# 05_LMS7002M_RF.net
KiCad netlist of a schematic drawn in Altium Designer
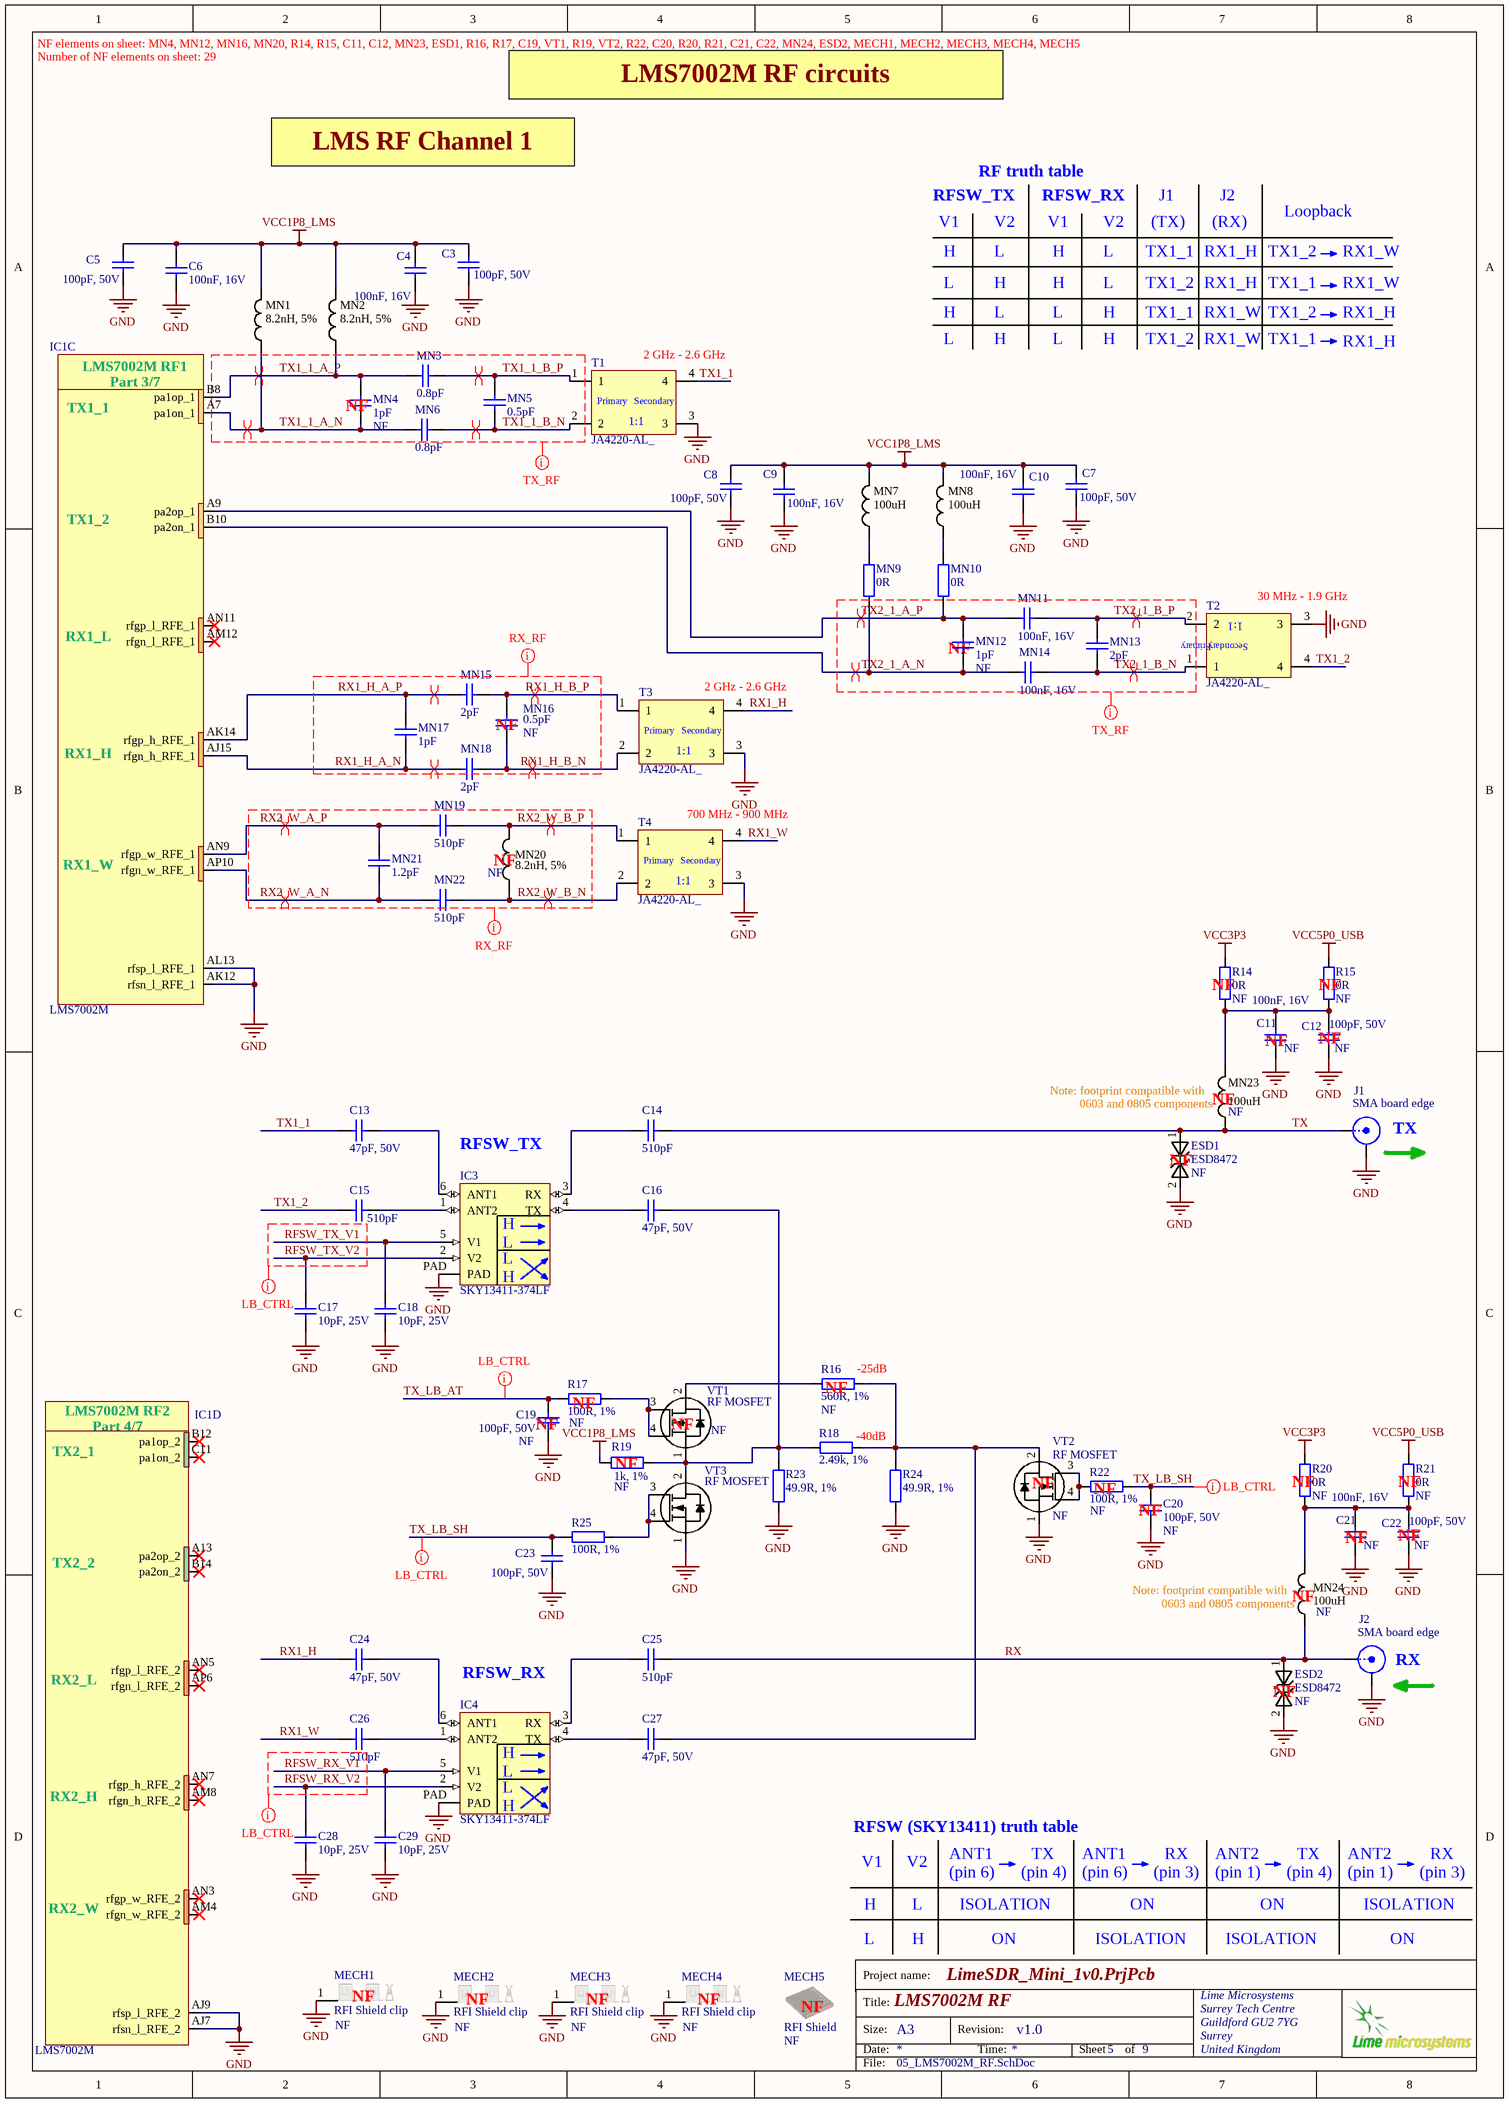
[diagram p0: 05_LMS7002M_RF.SchDoc]

(export (version "E")
  (design (tool "Eeschema 10.0.6"))
  (components
    (comp (ref "C3")
      (value "100pF, 50V")
      (footprint "CAP0402")
      (fields (field (name "TOLERANCE") "±5%") (field (name "MANUFACTURER") "Yageo"))
      (libsource (lib "LimeMicroAltiumLib_schLib") (part "Cap_0402"))
    )
    (comp (ref "C4")
      (value "100nF, 16V")
      (footprint "CAP0402")
      (fields
        (field (name "MANUFACTURER") "Murata Electronics")
        (field (name "TOLERANCE") "10 %")
        (field (name "MANUFACTURER PART NUMBER") "GRM155R71C104KA88D")
      )
      (libsource (lib "LimeMicroAltiumLib_schLib") (part "Cap_0402"))
    )
    (comp (ref "C5")
      (value "100pF, 50V")
      (footprint "CAP0402")
      (fields (field (name "TOLERANCE") "±5%") (field (name "MANUFACTURER") "Yageo"))
      (libsource (lib "LimeMicroAltiumLib_schLib") (part "Cap_0402"))
    )
    (comp (ref "C6")
      (value "100nF, 16V")
      (footprint "CAP0402")
      (fields
        (field (name "MANUFACTURER") "Murata Electronics")
        (field (name "TOLERANCE") "10 %")
        (field (name "MANUFACTURER PART NUMBER") "GRM155R71C104KA88D")
      )
      (libsource (lib "LimeMicroAltiumLib_schLib") (part "Cap_0402"))
    )
    (comp (ref "C7")
      (value "100pF, 50V")
      (footprint "CAP0402")
      (fields (field (name "TOLERANCE") "±5%") (field (name "MANUFACTURER") "Yageo"))
      (libsource (lib "LimeMicroAltiumLib_schLib") (part "Cap_0402"))
    )
    (comp (ref "C8")
      (value "100pF, 50V")
      (footprint "CAP0402")
      (fields (field (name "TOLERANCE") "±5%") (field (name "MANUFACTURER") "Yageo"))
      (libsource (lib "LimeMicroAltiumLib_schLib") (part "Cap_0402"))
    )
    (comp (ref "C9")
      (value "100nF, 16V")
      (footprint "CAP0402")
      (fields
        (field (name "MANUFACTURER") "Murata Electronics")
        (field (name "TOLERANCE") "10 %")
        (field (name "MANUFACTURER PART NUMBER") "GRM155R71C104KA88D")
      )
      (libsource (lib "LimeMicroAltiumLib_schLib") (part "Cap_0402"))
    )
    (comp (ref "C10")
      (value "100nF, 16V")
      (footprint "CAP0402")
      (fields
        (field (name "MANUFACTURER") "Murata Electronics")
        (field (name "TOLERANCE") "10 %")
        (field (name "MANUFACTURER PART NUMBER") "GRM155R71C104KA88D")
      )
      (libsource (lib "LimeMicroAltiumLib_schLib") (part "Cap_0402"))
    )
    (comp (ref "C11")
      (value "100nF, 16V")
      (footprint "CAP0402")
      (fields
        (field (name "ASSEMBLY INFO") "NF")
        (field (name "MANUFACTURER") "Murata Electronics")
        (field (name "TOLERANCE") "10 %")
        (field (name "MANUFACTURER PART NUMBER") "GRM155R71C104KA88D")
      )
      (libsource (lib "LimeMicroAltiumLib_schLib") (part "Cap_0402"))
    )
    (comp (ref "C12")
      (value "100pF, 50V")
      (footprint "CAP0402")
      (fields
        (field (name "ASSEMBLY INFO") "NF")
        (field (name "TOLERANCE") "±5%")
        (field (name "MANUFACTURER") "Yageo")
      )
      (libsource (lib "LimeMicroAltiumLib_schLib") (part "Cap_0402"))
    )
    (comp (ref "C13")
      (value "47pF, 50V")
      (footprint "CAP0402")
      (fields (field (name "TOLERANCE") "±1%") (field (name "MANUFACTURER") "TDK Corporation"))
      (libsource (lib "LimeMicroAltiumLib_schLib") (part "Cap_0402"))
    )
    (comp (ref "C14")
      (value "510pF")
      (footprint "CAP0402")
      (fields
        (field (name "TOLERANCE") "±5%")
        (field (name "MANUFACTURER") "Murata Electronics North America")
        (field (name "MANUFACTURER PART NUMBER") "GRM1555C1H511JA01D")
      )
      (libsource (lib "LimeMicroAltiumLib_schLib") (part "Cap_0402"))
    )
    (comp (ref "C15")
      (value "510pF")
      (footprint "CAP0402")
      (fields
        (field (name "TOLERANCE") "±5%")
        (field (name "MANUFACTURER") "Murata Electronics North America")
        (field (name "MANUFACTURER PART NUMBER") "GRM1555C1H511JA01D")
      )
      (libsource (lib "LimeMicroAltiumLib_schLib") (part "Cap_0402"))
    )
    (comp (ref "C16")
      (value "47pF, 50V")
      (footprint "CAP0402")
      (fields (field (name "TOLERANCE") "±1%") (field (name "MANUFACTURER") "TDK Corporation"))
      (libsource (lib "LimeMicroAltiumLib_schLib") (part "Cap_0402"))
    )
    (comp (ref "C17")
      (value "10pF, 25V")
      (footprint "CAP0402")
      (fields (field (name "MANUFACTURER") "AVX"))
      (libsource (lib "LimeFPGAboard_schLib") (part "Cap_0402"))
    )
    (comp (ref "C18")
      (value "10pF, 25V")
      (footprint "CAP0402")
      (fields (field (name "MANUFACTURER") "AVX"))
      (libsource (lib "LimeFPGAboard_schLib") (part "Cap_0402"))
    )
    (comp (ref "C19")
      (value "100pF, 50V")
      (footprint "CAP0402")
      (fields
        (field (name "ASSEMBLY INFO") "NF")
        (field (name "TOLERANCE") "±5%")
        (field (name "MANUFACTURER") "Yageo")
      )
      (libsource (lib "LimeMicroAltiumLib_schLib") (part "Cap_0402"))
    )
    (comp (ref "C20")
      (value "100pF, 50V")
      (footprint "CAP0402")
      (fields
        (field (name "ASSEMBLY INFO") "NF")
        (field (name "TOLERANCE") "±5%")
        (field (name "MANUFACTURER") "Yageo")
      )
      (libsource (lib "LimeMicroAltiumLib_schLib") (part "Cap_0402"))
    )
    (comp (ref "C21")
      (value "100nF, 16V")
      (footprint "CAP0402")
      (fields
        (field (name "ASSEMBLY INFO") "NF")
        (field (name "MANUFACTURER") "Murata Electronics")
        (field (name "TOLERANCE") "10 %")
        (field (name "MANUFACTURER PART NUMBER") "GRM155R71C104KA88D")
      )
      (libsource (lib "LimeMicroAltiumLib_schLib") (part "Cap_0402"))
    )
    (comp (ref "C22")
      (value "100pF, 50V")
      (footprint "CAP0402")
      (fields
        (field (name "ASSEMBLY INFO") "NF")
        (field (name "TOLERANCE") "±5%")
        (field (name "MANUFACTURER") "Yageo")
      )
      (libsource (lib "LimeMicroAltiumLib_schLib") (part "Cap_0402"))
    )
    (comp (ref "C23")
      (value "100pF, 50V")
      (footprint "CAP0402")
      (fields (field (name "TOLERANCE") "±5%") (field (name "MANUFACTURER") "Yageo"))
      (libsource (lib "LimeMicroAltiumLib_schLib") (part "Cap_0402"))
    )
    (comp (ref "C24")
      (value "47pF, 50V")
      (footprint "CAP0402")
      (fields (field (name "TOLERANCE") "±1%") (field (name "MANUFACTURER") "TDK Corporation"))
      (libsource (lib "LimeMicroAltiumLib_schLib") (part "Cap_0402"))
    )
    (comp (ref "C25")
      (value "510pF")
      (footprint "CAP0402")
      (fields
        (field (name "TOLERANCE") "±5%")
        (field (name "MANUFACTURER") "Murata Electronics North America")
        (field (name "MANUFACTURER PART NUMBER") "GRM1555C1H511JA01D")
      )
      (libsource (lib "LimeMicroAltiumLib_schLib") (part "Cap_0402"))
    )
    (comp (ref "C26")
      (value "510pF")
      (footprint "CAP0402")
      (fields
        (field (name "TOLERANCE") "±5%")
        (field (name "MANUFACTURER") "Murata Electronics North America")
        (field (name "MANUFACTURER PART NUMBER") "GRM1555C1H511JA01D")
      )
      (libsource (lib "LimeMicroAltiumLib_schLib") (part "Cap_0402"))
    )
    (comp (ref "C27")
      (value "47pF, 50V")
      (footprint "CAP0402")
      (fields (field (name "TOLERANCE") "±1%") (field (name "MANUFACTURER") "TDK Corporation"))
      (libsource (lib "LimeMicroAltiumLib_schLib") (part "Cap_0402"))
    )
    (comp (ref "C28")
      (value "10pF, 25V")
      (footprint "CAP0402")
      (fields (field (name "MANUFACTURER") "AVX"))
      (libsource (lib "LimeFPGAboard_schLib") (part "Cap_0402"))
    )
    (comp (ref "C29")
      (value "10pF, 25V")
      (footprint "CAP0402")
      (fields (field (name "MANUFACTURER") "AVX"))
      (libsource (lib "LimeFPGAboard_schLib") (part "Cap_0402"))
    )
    (comp (ref "ESD1")
      (value "ESD8472")
      (footprint "ESD8472_X3DFN2")
      (fields
        (field (name "MANUFACTURER") "ON Semiconductor")
        (field (name "MANUFACTURER PART NUMBER") "ESD8472MUT5G")
        (field (name "ASSEMBLY INFO") "NF")
      )
      (libsource (lib "LimeMicroAltiumLib_schLib") (part "ESD8472"))
    )
    (comp (ref "ESD2")
      (value "ESD8472")
      (footprint "ESD8472_X3DFN2")
      (fields
        (field (name "MANUFACTURER") "ON Semiconductor")
        (field (name "MANUFACTURER PART NUMBER") "ESD8472MUT5G")
        (field (name "ASSEMBLY INFO") "NF")
      )
      (libsource (lib "LimeMicroAltiumLib_schLib") (part "ESD8472"))
    )
    (comp (ref "IC1")
      (value "LMS7002M")
      (footprint "LMS7002M_v4")
      (description "Schematic symbol revision 3. Default footprint - 0.31mm pad")
      (fields (field (name "MANUFACTURER") "Lime Microsystems"))
      (libsource (lib "LimeMicroAltiumLib_schLib") (part "LMS7002Mr3"))
    )
    (comp (ref "IC3")
      (value "SKY13411-374LF")
      (footprint "SKY13411-374LF")
      (fields (field (name "MANUFACTURER") "Skyworks Solutions Inc."))
      (libsource (lib "LimeMicroAltiumLib_schLib") (part "SKY13411-374LF"))
    )
    (comp (ref "IC4")
      (value "SKY13411-374LF")
      (footprint "SKY13411-374LF")
      (fields (field (name "MANUFACTURER") "Skyworks Solutions Inc."))
      (libsource (lib "LimeMicroAltiumLib_schLib") (part "SKY13411-374LF"))
    )
    (comp (ref "J1")
      (value "SMA board edge")
      (footprint "SMA_connector_board_edge_SM")
      (description "CONN SMA JACK STR 50OHM EDGE MNT")
      (fields (field (name "MANUFACTURER") "RF Solutions"))
      (libsource (lib "LimeMicroAltiumLib_schLib") (part "RF_IF_connector"))
    )
    (comp (ref "J2")
      (value "SMA board edge")
      (footprint "SMA_connector_board_edge_SM")
      (description "CONN SMA JACK STR 50OHM EDGE MNT")
      (fields (field (name "MANUFACTURER") "RF Solutions"))
      (libsource (lib "LimeMicroAltiumLib_schLib") (part "RF_IF_connector"))
    )
    (comp (ref "MECH1")
      (value "RFI Shield clip")
      (footprint "RFI_SHIELD_CLPS_MINI")
      (fields (field (name "MANUFACTURER") "HARWIN") (field (name "ASSEMBLY INFO") "NF"))
      (libsource (lib "LimeMicroAltiumLib_schLib") (part "RFI_SHIELD_CLIP"))
    )
    (comp (ref "MECH2")
      (value "RFI Shield clip")
      (footprint "RFI_SHIELD_CLPS_MINI")
      (fields (field (name "MANUFACTURER") "HARWIN") (field (name "ASSEMBLY INFO") "NF"))
      (libsource (lib "LimeMicroAltiumLib_schLib") (part "RFI_SHIELD_CLIP"))
    )
    (comp (ref "MECH3")
      (value "RFI Shield clip")
      (footprint "RFI_SHIELD_CLPS_MINI")
      (fields (field (name "MANUFACTURER") "HARWIN") (field (name "ASSEMBLY INFO") "NF"))
      (libsource (lib "LimeMicroAltiumLib_schLib") (part "RFI_SHIELD_CLIP"))
    )
    (comp (ref "MECH4")
      (value "RFI Shield clip")
      (footprint "RFI_SHIELD_CLPS_MINI")
      (fields (field (name "MANUFACTURER") "HARWIN") (field (name "ASSEMBLY INFO") "NF"))
      (libsource (lib "LimeMicroAltiumLib_schLib") (part "RFI_SHIELD_CLIP"))
    )
    (comp (ref "MECH5")
      (value "RFI Shield")
      (footprint "WurthElectronic_RF_shield")
      (fields (field (name "MANUFACTURER") "WURTH ELEKTRONIK") (field (name "ASSEMBLY INFO") "NF"))
      (libsource (lib "LimeMicroAltiumLib_schLib") (part "RFI_SHIELD_1"))
    )
    (comp (ref "MN1")
      (value "8.2nH, 5%")
      (footprint "RES0402")
      (fields (field (name "MANUFACTURER") "COILCRAFT"))
      (libsource (lib "LimeMicroAltiumLib_schLib") (part "Inductor_0603"))
    )
    (comp (ref "MN2")
      (value "8.2nH, 5%")
      (footprint "RES0402")
      (fields (field (name "MANUFACTURER") "COILCRAFT"))
      (libsource (lib "LimeMicroAltiumLib_schLib") (part "Inductor_0603"))
    )
    (comp (ref "MN3")
      (value "0.8pF")
      (footprint "CAP0402")
      (fields
        (field (name "TOLERANCE") "±0.1pF")
        (field (name "MANUFACTURER") "Murata Electronics North America")
        (field (name "MANUFACTURER PART NUMBER") "GRM1555C1HR80BA01D")
      )
      (libsource (lib "LimeMicroAltiumLib_schLib") (part "Cap_0402"))
    )
    (comp (ref "MN4")
      (value "1pF")
      (footprint "CAP0402")
      (fields
        (field (name "ASSEMBLY INFO") "NF")
        (field (name "MANUFACTURER") "TDK Corporation")
        (field (name "TOLERANCE") "±0.1pF")
      )
      (libsource (lib "LimeMicroAltiumLib_schLib") (part "Cap_0402"))
    )
    (comp (ref "MN5")
      (value "0.5pF")
      (footprint "CAP0402")
      (fields (field (name "TOLERANCE") "±0.25pF") (field (name "MANUFACTURER") "Yageo"))
      (libsource (lib "LimeMicroAltiumLib_schLib") (part "Cap_0402"))
    )
    (comp (ref "MN6")
      (value "0.8pF")
      (footprint "CAP0402")
      (fields
        (field (name "TOLERANCE") "±0.1pF")
        (field (name "MANUFACTURER") "Murata Electronics North America")
        (field (name "MANUFACTURER PART NUMBER") "GRM1555C1HR80BA01D")
      )
      (libsource (lib "LimeMicroAltiumLib_schLib") (part "Cap_0402"))
    )
    (comp (ref "MN7")
      (value "100uH")
      (footprint "RES0805")
      (fields
        (field (name "TOLERANCE") "±10%")
        (field (name "MANUFACTURER") "TDK Corporation")
        (field (name "MANUFACTURER PART NUMBER") "MLF2012C101KT000")
      )
      (libsource (lib "LimeMicroAltiumLib_schLib") (part "Inductor_0603"))
    )
    (comp (ref "MN8")
      (value "100uH")
      (footprint "RES0805")
      (fields
        (field (name "TOLERANCE") "±10%")
        (field (name "MANUFACTURER") "TDK Corporation")
        (field (name "MANUFACTURER PART NUMBER") "MLF2012C101KT000")
      )
      (libsource (lib "LimeMicroAltiumLib_schLib") (part "Inductor_0603"))
    )
    (comp (ref "MN9")
      (value "0R")
      (footprint "RES0402")
      (fields (field (name "MANUFACTURER") "Yageo"))
      (libsource (lib "LimeFPGAboard_schLib") (part "Res_0402"))
    )
    (comp (ref "MN10")
      (value "0R")
      (footprint "RES0402")
      (fields (field (name "MANUFACTURER") "Yageo"))
      (libsource (lib "LimeFPGAboard_schLib") (part "Res_0402"))
    )
    (comp (ref "MN11")
      (value "100nF, 16V")
      (footprint "CAP0402")
      (fields
        (field (name "MANUFACTURER") "Murata Electronics")
        (field (name "TOLERANCE") "10 %")
        (field (name "MANUFACTURER PART NUMBER") "GRM155R71C104KA88D")
      )
      (libsource (lib "LimeMicroAltiumLib_schLib") (part "Cap_0402"))
    )
    (comp (ref "MN12")
      (value "1pF")
      (footprint "CAP0402")
      (fields
        (field (name "ASSEMBLY INFO") "NF")
        (field (name "MANUFACTURER") "TDK Corporation")
        (field (name "TOLERANCE") "±0.1pF")
      )
      (libsource (lib "LimeMicroAltiumLib_schLib") (part "Cap_0402"))
    )
    (comp (ref "MN13")
      (value "2pF")
      (footprint "CAP0402")
      (fields (field (name "MANUFACTURER PART NUMBER") "04025U2R0BAT2A") (field (name "MANUFACTURER") "AVX"))
      (libsource (lib "LimeMicroAltiumLib_schLib") (part "Cap_0402"))
    )
    (comp (ref "MN14")
      (value "100nF, 16V")
      (footprint "CAP0402")
      (fields
        (field (name "MANUFACTURER") "Murata Electronics")
        (field (name "TOLERANCE") "10 %")
        (field (name "MANUFACTURER PART NUMBER") "GRM155R71C104KA88D")
      )
      (libsource (lib "LimeMicroAltiumLib_schLib") (part "Cap_0402"))
    )
    (comp (ref "MN15")
      (value "2pF")
      (footprint "CAP0402")
      (fields (field (name "MANUFACTURER PART NUMBER") "04025U2R0BAT2A") (field (name "MANUFACTURER") "AVX"))
      (libsource (lib "LimeMicroAltiumLib_schLib") (part "Cap_0402"))
    )
    (comp (ref "MN16")
      (value "0.5pF")
      (footprint "CAP0402")
      (fields
        (field (name "ASSEMBLY INFO") "NF")
        (field (name "TOLERANCE") "±0.25pF")
        (field (name "MANUFACTURER") "Yageo")
      )
      (libsource (lib "LimeMicroAltiumLib_schLib") (part "Cap_0402"))
    )
    (comp (ref "MN17")
      (value "1pF")
      (footprint "CAP0402")
      (fields (field (name "MANUFACTURER") "TDK Corporation") (field (name "TOLERANCE") "±0.1pF"))
      (libsource (lib "LimeMicroAltiumLib_schLib") (part "Cap_0402"))
    )
    (comp (ref "MN18")
      (value "2pF")
      (footprint "CAP0402")
      (fields (field (name "MANUFACTURER PART NUMBER") "04025U2R0BAT2A") (field (name "MANUFACTURER") "AVX"))
      (libsource (lib "LimeMicroAltiumLib_schLib") (part "Cap_0402"))
    )
    (comp (ref "MN19")
      (value "510pF")
      (footprint "CAP0402")
      (fields
        (field (name "TOLERANCE") "±5%")
        (field (name "MANUFACTURER") "Murata Electronics North America")
        (field (name "MANUFACTURER PART NUMBER") "GRM1555C1H511JA01D")
      )
      (libsource (lib "LimeMicroAltiumLib_schLib") (part "Cap_0402"))
    )
    (comp (ref "MN20")
      (value "8.2nH, 5%")
      (footprint "RES0402")
      (fields (field (name "MANUFACTURER") "COILCRAFT") (field (name "ASSEMBLY INFO") "NF"))
      (libsource (lib "LimeMicroAltiumLib_schLib") (part "Inductor_0603"))
    )
    (comp (ref "MN21")
      (value "1.2pF")
      (footprint "CAP0402")
      (fields
        (field (name "MANUFACTURER") "Murata Electronics North America")
        (field (name "TOLERANCE") "±0.25pF")
      )
      (libsource (lib "LimeMicroAltiumLib_schLib") (part "Cap_0402"))
    )
    (comp (ref "MN22")
      (value "510pF")
      (footprint "CAP0402")
      (fields
        (field (name "TOLERANCE") "±5%")
        (field (name "MANUFACTURER") "Murata Electronics North America")
        (field (name "MANUFACTURER PART NUMBER") "GRM1555C1H511JA01D")
      )
      (libsource (lib "LimeMicroAltiumLib_schLib") (part "Cap_0402"))
    )
    (comp (ref "MN23")
      (value "100uH")
      (footprint "RES0805_0603")
      (fields
        (field (name "TOLERANCE") "±10%")
        (field (name "MANUFACTURER") "TDK Corporation")
        (field (name "MANUFACTURER PART NUMBER") "MLF2012C101KT000")
        (field (name "ASSEMBLY INFO") "NF")
      )
      (libsource (lib "LimeMicroAltiumLib_schLib") (part "Inductor_0603"))
    )
    (comp (ref "MN24")
      (value "100uH")
      (footprint "RES0805_0603")
      (fields
        (field (name "TOLERANCE") "±10%")
        (field (name "MANUFACTURER") "TDK Corporation")
        (field (name "MANUFACTURER PART NUMBER") "MLF2012C101KT000")
        (field (name "ASSEMBLY INFO") "NF")
      )
      (libsource (lib "LimeMicroAltiumLib_schLib") (part "Inductor_0603"))
    )
    (comp (ref "R14")
      (value "0R")
      (footprint "RES0402")
      (fields (field (name "MANUFACTURER") "Yageo") (field (name "ASSEMBLY INFO") "NF"))
      (libsource (lib "LimeFPGAboard_schLib") (part "Res_0402"))
    )
    (comp (ref "R15")
      (value "0R")
      (footprint "RES0402")
      (fields (field (name "MANUFACTURER") "Yageo") (field (name "ASSEMBLY INFO") "NF"))
      (libsource (lib "LimeFPGAboard_schLib") (part "Res_0402"))
    )
    (comp (ref "R16")
      (value "560R, 1%")
      (footprint "RES0402")
      (fields
        (field (name "ASSEMBLY INFO") "NF")
        (field (name "MANUFACTURER PART NUMBER") "CRCW0402560RFKED")
        (field (name "TOLERANCE") "±1%")
        (field (name "MANUFACTURER") "Vishay Dale")
      )
      (libsource (lib "LimeMicroAltiumLib_schLib") (part "Res_0402"))
    )
    (comp (ref "R17")
      (value "100R, 1%")
      (footprint "RES0402")
      (fields
        (field (name "TOLERANCE") "±1%")
        (field (name "MANUFACTURER") "Stackpole Electronics Inc.")
        (field (name "ASSEMBLY INFO") "NF")
      )
      (libsource (lib "LimeFPGAboard_schLib") (part "Res_0402"))
    )
    (comp (ref "R18")
      (value "2.49k, 1%")
      (footprint "RES0402")
      (fields
        (field (name "TOLERANCE") "±1%")
        (field (name "MANUFACTURER PART NUMBER") "RC0402FR-072K49L")
        (field (name "MANUFACTURER") "Yageo")
      )
      (libsource (lib "LimeMicroAltiumLib_schLib") (part "Res_0402"))
    )
    (comp (ref "R19")
      (value "1k, 1%")
      (footprint "RES0402")
      (fields
        (field (name "ASSEMBLY INFO") "NF")
        (field (name "MANUFACTURER") "Stackpole Electronics Inc")
        (field (name "TOLERANCE") "±1%")
      )
      (libsource (lib "LimeMicroAltiumLib_schLib") (part "Res_0402"))
    )
    (comp (ref "R20")
      (value "0R")
      (footprint "RES0402")
      (fields (field (name "MANUFACTURER") "Yageo") (field (name "ASSEMBLY INFO") "NF"))
      (libsource (lib "LimeFPGAboard_schLib") (part "Res_0402"))
    )
    (comp (ref "R21")
      (value "0R")
      (footprint "RES0402")
      (fields (field (name "MANUFACTURER") "Yageo") (field (name "ASSEMBLY INFO") "NF"))
      (libsource (lib "LimeFPGAboard_schLib") (part "Res_0402"))
    )
    (comp (ref "R22")
      (value "100R, 1%")
      (footprint "RES0402")
      (fields
        (field (name "TOLERANCE") "±1%")
        (field (name "MANUFACTURER") "Stackpole Electronics Inc.")
        (field (name "ASSEMBLY INFO") "NF")
      )
      (libsource (lib "LimeFPGAboard_schLib") (part "Res_0402"))
    )
    (comp (ref "R23")
      (value "49.9R, 1%")
      (footprint "RES0402")
      (fields
        (field (name "TOLERANCE") "±1%")
        (field (name "MANUFACTURER") "Samsung Electro-Mechanics America, Inc.")
        (field (name "MANUFACTURER PART NUMBER") "RC1005F49R9CS")
      )
      (libsource (lib "LimeMicroAltiumLib_schLib") (part "Res_0402"))
    )
    (comp (ref "R24")
      (value "49.9R, 1%")
      (footprint "RES0402")
      (fields
        (field (name "TOLERANCE") "±1%")
        (field (name "MANUFACTURER") "Samsung Electro-Mechanics America, Inc.")
        (field (name "MANUFACTURER PART NUMBER") "RC1005F49R9CS")
      )
      (libsource (lib "LimeMicroAltiumLib_schLib") (part "Res_0402"))
    )
    (comp (ref "R25")
      (value "100R, 1%")
      (footprint "RES0402")
      (fields (field (name "TOLERANCE") "±1%") (field (name "MANUFACTURER") "Stackpole Electronics Inc."))
      (libsource (lib "LimeFPGAboard_schLib") (part "Res_0402"))
    )
    (comp (ref "T1")
      (value "JA4220-AL_")
      (footprint "JA4220-AL_")
      (fields (field (name "MANUFACTURER") "Coilcraft"))
      (libsource (lib "LimeMicroAltiumLib_schLib") (part "JA4220-AL_"))
    )
    (comp (ref "T2")
      (value "JA4220-AL_")
      (footprint "JA4220-AL_")
      (fields (field (name "MANUFACTURER") "Coilcraft"))
      (libsource (lib "") (part "JA4220-AL__1"))
    )
    (comp (ref "T3")
      (value "JA4220-AL_")
      (footprint "JA4220-AL_")
      (fields (field (name "MANUFACTURER") "Coilcraft"))
      (libsource (lib "LimeMicroAltiumLib_schLib") (part "JA4220-AL_"))
    )
    (comp (ref "T4")
      (value "JA4220-AL_")
      (footprint "JA4220-AL_")
      (fields (field (name "MANUFACTURER") "Coilcraft"))
      (libsource (lib "LimeMicroAltiumLib_schLib") (part "JA4220-AL_"))
    )
    (comp (ref "VT1")
      (value "RF MOSFET")
      (footprint "BF1105R_SOT143R4")
      (fields (field (name "MANUFACTURER") "NXP Semiconductors") (field (name "ASSEMBLY INFO") "NF"))
      (libsource (lib "LimeMicroAltiumLib_schLib") (part "BF1105R,215"))
    )
    (comp (ref "VT2")
      (value "RF MOSFET")
      (footprint "BF1105R_SOT143R4")
      (fields (field (name "MANUFACTURER") "NXP Semiconductors") (field (name "ASSEMBLY INFO") "NF"))
      (libsource (lib "LimeMicroAltiumLib_schLib") (part "BF1105R,215"))
    )
    (comp (ref "VT3")
      (value "RF MOSFET")
      (footprint "BF1105R_SOT143R4")
      (fields (field (name "MANUFACTURER") "NXP Semiconductors"))
      (libsource (lib "LimeMicroAltiumLib_schLib") (part "BF1105R,215"))
    )
  )
  (nets
    (net (code "1") (name "/RFSW_RX_V1") (class "Default")
      (node (ref "C29") (pin "2") (pinfunction "2_2") (pintype "passive"))
      (node (ref "IC4") (pin "5") (pinfunction "V1_5") (pintype "input"))
    )
    (net (code "2") (name "/RFSW_RX_V2") (class "Default")
      (node (ref "C28") (pin "2") (pinfunction "2_2") (pintype "passive"))
      (node (ref "IC4") (pin "2") (pinfunction "V2_2") (pintype "input"))
    )
    (net (code "3") (name "/RFSW_TX_V1") (class "Default")
      (node (ref "C18") (pin "2") (pinfunction "2_2") (pintype "passive"))
      (node (ref "IC3") (pin "5") (pinfunction "V1_5") (pintype "input"))
    )
    (net (code "4") (name "/RFSW_TX_V2") (class "Default")
      (node (ref "C17") (pin "2") (pinfunction "2_2") (pintype "passive"))
      (node (ref "IC3") (pin "2") (pinfunction "V2_2") (pintype "input"))
    )
    (net (code "5") (name "/RX") (class "Default")
      (node (ref "C25") (pin "2") (pinfunction "2_2") (pintype "passive"))
      (node (ref "ESD2") (pin "1") (pinfunction "1_1") (pintype "passive"))
      (node (ref "J2") (pin "1") (pinfunction "X_1") (pintype "passive"))
      (node (ref "MN24") (pin "1") (pinfunction "1_1") (pintype "passive"))
    )
    (net (code "6") (name "/RX1_H") (class "Default")
      (node (ref "C24") (pin "2") (pinfunction "2_2") (pintype "passive"))
      (node (ref "T3") (pin "4") (pinfunction "4_4") (pintype "passive"))
    )
    (net (code "7") (name "/RX1_H_A_N") (class "Default")
      (node (ref "IC1") (pin "AJ15") (pinfunction "rfgn_h_RFE_1_AJ15") (pintype "passive"))
      (node (ref "MN17") (pin "1") (pinfunction "1_1") (pintype "passive"))
      (node (ref "MN18") (pin "2") (pinfunction "2_2") (pintype "passive"))
    )
    (net (code "8") (name "/RX1_H_A_P") (class "Default")
      (node (ref "IC1") (pin "AK14") (pinfunction "rfgp_h_RFE_1_AK14") (pintype "passive"))
      (node (ref "MN15") (pin "2") (pinfunction "2_2") (pintype "passive"))
      (node (ref "MN17") (pin "2") (pinfunction "2_2") (pintype "passive"))
    )
    (net (code "9") (name "/RX1_H_B_N") (class "Default")
      (node (ref "MN16") (pin "1") (pinfunction "1_1") (pintype "passive"))
      (node (ref "MN18") (pin "1") (pinfunction "1_1") (pintype "passive"))
      (node (ref "T3") (pin "2") (pinfunction "2_2") (pintype "passive"))
    )
    (net (code "10") (name "/RX1_H_B_P") (class "Default")
      (node (ref "MN15") (pin "1") (pinfunction "1_1") (pintype "passive"))
      (node (ref "MN16") (pin "2") (pinfunction "2_2") (pintype "passive"))
      (node (ref "T3") (pin "1") (pinfunction "1_1") (pintype "passive"))
    )
    (net (code "11") (name "/RX1_W") (class "Default")
      (node (ref "C26") (pin "2") (pinfunction "2_2") (pintype "passive"))
      (node (ref "T4") (pin "4") (pinfunction "4_4") (pintype "passive"))
    )
    (net (code "12") (name "/RX2_W_A_N") (class "Default")
      (node (ref "IC1") (pin "AP10") (pinfunction "rfgn_w_RFE_1_AP10") (pintype "passive"))
      (node (ref "MN21") (pin "1") (pinfunction "1_1") (pintype "passive"))
      (node (ref "MN22") (pin "2") (pinfunction "2_2") (pintype "passive"))
    )
    (net (code "13") (name "/RX2_W_A_P") (class "Default")
      (node (ref "IC1") (pin "AN9") (pinfunction "rfgp_w_RFE_1_AN9") (pintype "passive"))
      (node (ref "MN19") (pin "2") (pinfunction "2_2") (pintype "passive"))
      (node (ref "MN21") (pin "2") (pinfunction "2_2") (pintype "passive"))
    )
    (net (code "14") (name "/RX2_W_B_N") (class "Default")
      (node (ref "MN20") (pin "1") (pinfunction "1_1") (pintype "passive"))
      (node (ref "MN22") (pin "1") (pinfunction "1_1") (pintype "passive"))
      (node (ref "T4") (pin "2") (pinfunction "2_2") (pintype "passive"))
    )
    (net (code "15") (name "/RX2_W_B_P") (class "Default")
      (node (ref "MN19") (pin "1") (pinfunction "1_1") (pintype "passive"))
      (node (ref "MN20") (pin "2") (pinfunction "2_2") (pintype "passive"))
      (node (ref "T4") (pin "1") (pinfunction "1_1") (pintype "passive"))
    )
    (net (code "16") (name "/TX") (class "Default")
      (node (ref "C14") (pin "2") (pinfunction "2_2") (pintype "passive"))
      (node (ref "ESD1") (pin "1") (pinfunction "1_1") (pintype "passive"))
      (node (ref "J1") (pin "1") (pinfunction "X_1") (pintype "passive"))
      (node (ref "MN23") (pin "1") (pinfunction "1_1") (pintype "passive"))
    )
    (net (code "17") (name "/TX1_1") (class "Default")
      (node (ref "C13") (pin "2") (pinfunction "2_2") (pintype "passive"))
      (node (ref "T1") (pin "4") (pinfunction "4_4") (pintype "passive"))
    )
    (net (code "18") (name "/TX1_1_A_N") (class "Default")
      (node (ref "IC1") (pin "A7") (pinfunction "pa1on_1_A7") (pintype "passive"))
      (node (ref "MN1") (pin "1") (pinfunction "1_1") (pintype "passive"))
      (node (ref "MN4") (pin "1") (pinfunction "1_1") (pintype "passive"))
      (node (ref "MN6") (pin "2") (pinfunction "2_2") (pintype "passive"))
    )
    (net (code "19") (name "/TX1_1_A_P") (class "Default")
      (node (ref "IC1") (pin "B8") (pinfunction "pa1op_1_B8") (pintype "passive"))
      (node (ref "MN2") (pin "1") (pinfunction "1_1") (pintype "passive"))
      (node (ref "MN3") (pin "1") (pinfunction "1_1") (pintype "passive"))
      (node (ref "MN4") (pin "2") (pinfunction "2_2") (pintype "passive"))
    )
    (net (code "20") (name "/TX1_1_B_N") (class "Default")
      (node (ref "MN5") (pin "2") (pinfunction "2_2") (pintype "passive"))
      (node (ref "MN6") (pin "1") (pinfunction "1_1") (pintype "passive"))
      (node (ref "T1") (pin "2") (pinfunction "2_2") (pintype "passive"))
    )
    (net (code "21") (name "/TX1_1_B_P") (class "Default")
      (node (ref "MN3") (pin "2") (pinfunction "2_2") (pintype "passive"))
      (node (ref "MN5") (pin "1") (pinfunction "1_1") (pintype "passive"))
      (node (ref "T1") (pin "1") (pinfunction "1_1") (pintype "passive"))
    )
    (net (code "22") (name "/TX1_2") (class "Default")
      (node (ref "C15") (pin "2") (pinfunction "2_2") (pintype "passive"))
      (node (ref "T2") (pin "4") (pinfunction "4_4") (pintype "passive"))
    )
    (net (code "23") (name "/TX2_1_A_N") (class "Default")
      (node (ref "IC1") (pin "B10") (pinfunction "pa2on_1_B10") (pintype "passive"))
      (node (ref "MN12") (pin "2") (pinfunction "2_2") (pintype "passive"))
      (node (ref "MN14") (pin "1") (pinfunction "1_1") (pintype "passive"))
      (node (ref "MN9") (pin "1") (pinfunction "1_1") (pintype "passive"))
    )
    (net (code "24") (name "/TX2_1_A_P") (class "Default")
      (node (ref "IC1") (pin "A9") (pinfunction "pa2op_1_A9") (pintype "passive"))
      (node (ref "MN10") (pin "1") (pinfunction "1_1") (pintype "passive"))
      (node (ref "MN11") (pin "2") (pinfunction "2_2") (pintype "passive"))
      (node (ref "MN12") (pin "1") (pinfunction "1_1") (pintype "passive"))
    )
    (net (code "25") (name "/TX2_1_B_N") (class "Default")
      (node (ref "MN13") (pin "1") (pinfunction "1_1") (pintype "passive"))
      (node (ref "MN14") (pin "2") (pinfunction "2_2") (pintype "passive"))
      (node (ref "T2") (pin "1") (pinfunction "1_1") (pintype "passive"))
    )
    (net (code "26") (name "/TX2_1_B_P") (class "Default")
      (node (ref "MN11") (pin "1") (pinfunction "1_1") (pintype "passive"))
      (node (ref "MN13") (pin "2") (pinfunction "2_2") (pintype "passive"))
      (node (ref "T2") (pin "2") (pinfunction "2_2") (pintype "passive"))
    )
    (net (code "27") (name "/TX_LB_AT") (class "Default")
      (node (ref "C19") (pin "1") (pinfunction "1_1") (pintype "passive"))
      (node (ref "R17") (pin "2") (pinfunction "2_2") (pintype "passive"))
    )
    (net (code "28") (name "/TX_LB_SH") (class "Default")
      (node (ref "C20") (pin "1") (pinfunction "1_1") (pintype "passive"))
      (node (ref "C23") (pin "1") (pinfunction "1_1") (pintype "passive"))
      (node (ref "R22") (pin "1") (pinfunction "1_1") (pintype "passive"))
      (node (ref "R25") (pin "2") (pinfunction "2_2") (pintype "passive"))
    )
    (net (code "29") (name "GND") (class "Default")
      (node (ref "C10") (pin "1") (pinfunction "1_1") (pintype "passive"))
      (node (ref "C11") (pin "1") (pinfunction "1_1") (pintype "passive"))
      (node (ref "C12") (pin "2") (pinfunction "2_2") (pintype "passive"))
      (node (ref "C17") (pin "1") (pinfunction "1_1") (pintype "passive"))
      (node (ref "C18") (pin "1") (pinfunction "1_1") (pintype "passive"))
      (node (ref "C19") (pin "2") (pinfunction "2_2") (pintype "passive"))
      (node (ref "C20") (pin "2") (pinfunction "2_2") (pintype "passive"))
      (node (ref "C21") (pin "1") (pinfunction "1_1") (pintype "passive"))
      (node (ref "C22") (pin "2") (pinfunction "2_2") (pintype "passive"))
      (node (ref "C23") (pin "2") (pinfunction "2_2") (pintype "passive"))
      (node (ref "C28") (pin "1") (pinfunction "1_1") (pintype "passive"))
      (node (ref "C29") (pin "1") (pinfunction "1_1") (pintype "passive"))
      (node (ref "C3") (pin "2") (pinfunction "2_2") (pintype "passive"))
      (node (ref "C4") (pin "1") (pinfunction "1_1") (pintype "passive"))
      (node (ref "C5") (pin "2") (pinfunction "2_2") (pintype "passive"))
      (node (ref "C6") (pin "1") (pinfunction "1_1") (pintype "passive"))
      (node (ref "C7") (pin "2") (pinfunction "2_2") (pintype "passive"))
      (node (ref "C8") (pin "2") (pinfunction "2_2") (pintype "passive"))
      (node (ref "C9") (pin "1") (pinfunction "1_1") (pintype "passive"))
      (node (ref "ESD1") (pin "2") (pinfunction "2_2") (pintype "passive"))
      (node (ref "ESD2") (pin "2") (pinfunction "2_2") (pintype "passive"))
      (node (ref "IC1") (pin "AJ7") (pinfunction "rfsn_l_RFE_2_AJ7") (pintype "passive"))
      (node (ref "IC1") (pin "AJ9") (pinfunction "rfsp_l_RFE_2_AJ9") (pintype "passive"))
      (node (ref "IC1") (pin "AK12") (pinfunction "rfsn_l_RFE_1_AK12") (pintype "passive"))
      (node (ref "IC1") (pin "AL13") (pinfunction "rfsp_l_RFE_1_AL13") (pintype "passive"))
      (node (ref "IC3") (pin "PAD") (pinfunction "PAD_PAD") (pintype "passive"))
      (node (ref "IC4") (pin "PAD") (pinfunction "PAD_PAD") (pintype "passive"))
      (node (ref "J1") (pin "2") (pinfunction "Y_2") (pintype "passive"))
      (node (ref "J2") (pin "2") (pinfunction "Y_2") (pintype "passive"))
      (node (ref "MECH1") (pin "1") (pinfunction "GND_1") (pintype "passive"))
      (node (ref "MECH2") (pin "1") (pinfunction "GND_1") (pintype "passive"))
      (node (ref "MECH3") (pin "1") (pinfunction "GND_1") (pintype "passive"))
      (node (ref "MECH4") (pin "1") (pinfunction "GND_1") (pintype "passive"))
      (node (ref "R23") (pin "1") (pinfunction "1_1") (pintype "passive"))
      (node (ref "R24") (pin "1") (pinfunction "1_1") (pintype "passive"))
      (node (ref "T1") (pin "3") (pinfunction "3_3") (pintype "passive"))
      (node (ref "T2") (pin "3") (pinfunction "3_3") (pintype "passive"))
      (node (ref "T3") (pin "3") (pinfunction "3_3") (pintype "passive"))
      (node (ref "T4") (pin "3") (pinfunction "3_3") (pintype "passive"))
      (node (ref "VT2") (pin "1") (pinfunction "S_1") (pintype "passive"))
      (node (ref "VT3") (pin "1") (pinfunction "S_1") (pintype "passive"))
    )
    (net (code "30") (name "Net-(C11-Pad2)") (class "Default")
      (node (ref "C11") (pin "2") (pinfunction "2_2") (pintype "passive"))
      (node (ref "C12") (pin "1") (pinfunction "1_1") (pintype "passive"))
      (node (ref "MN23") (pin "2") (pinfunction "2_2") (pintype "passive"))
      (node (ref "R14") (pin "2") (pinfunction "2_2") (pintype "passive"))
      (node (ref "R15") (pin "2") (pinfunction "2_2") (pintype "passive"))
    )
    (net (code "31") (name "Net-(C21-Pad2)") (class "Default")
      (node (ref "C21") (pin "2") (pinfunction "2_2") (pintype "passive"))
      (node (ref "C22") (pin "1") (pinfunction "1_1") (pintype "passive"))
      (node (ref "MN24") (pin "2") (pinfunction "2_2") (pintype "passive"))
      (node (ref "R20") (pin "2") (pinfunction "2_2") (pintype "passive"))
      (node (ref "R21") (pin "2") (pinfunction "2_2") (pintype "passive"))
    )
    (net (code "32") (name "Net-(IC3-ANT1)") (class "Default")
      (node (ref "C13") (pin "1") (pinfunction "1_1") (pintype "passive"))
      (node (ref "IC3") (pin "6") (pinfunction "ANT1_6") (pintype "bidirectional"))
    )
    (net (code "33") (name "Net-(IC3-ANT2)") (class "Default")
      (node (ref "C15") (pin "1") (pinfunction "1_1") (pintype "passive"))
      (node (ref "IC3") (pin "1") (pinfunction "ANT2_1") (pintype "bidirectional"))
    )
    (net (code "34") (name "Net-(IC3-RX)") (class "Default")
      (node (ref "C14") (pin "1") (pinfunction "1_1") (pintype "passive"))
      (node (ref "IC3") (pin "3") (pinfunction "RX_3") (pintype "bidirectional"))
    )
    (net (code "35") (name "Net-(IC3-TX)") (class "Default")
      (node (ref "C16") (pin "1") (pinfunction "1_1") (pintype "passive"))
      (node (ref "IC3") (pin "4") (pinfunction "TX_4") (pintype "bidirectional"))
    )
    (net (code "36") (name "Net-(IC4-ANT1)") (class "Default")
      (node (ref "C24") (pin "1") (pinfunction "1_1") (pintype "passive"))
      (node (ref "IC4") (pin "6") (pinfunction "ANT1_6") (pintype "bidirectional"))
    )
    (net (code "37") (name "Net-(IC4-ANT2)") (class "Default")
      (node (ref "C26") (pin "1") (pinfunction "1_1") (pintype "passive"))
      (node (ref "IC4") (pin "1") (pinfunction "ANT2_1") (pintype "bidirectional"))
    )
    (net (code "38") (name "Net-(IC4-RX)") (class "Default")
      (node (ref "C25") (pin "1") (pinfunction "1_1") (pintype "passive"))
      (node (ref "IC4") (pin "3") (pinfunction "RX_3") (pintype "bidirectional"))
    )
    (net (code "39") (name "Net-(IC4-TX)") (class "Default")
      (node (ref "C27") (pin "1") (pinfunction "1_1") (pintype "passive"))
      (node (ref "IC4") (pin "4") (pinfunction "TX_4") (pintype "bidirectional"))
    )
    (net (code "40") (name "Net-(MN7-Pad1)") (class "Default")
      (node (ref "MN7") (pin "1") (pinfunction "1_1") (pintype "passive"))
      (node (ref "MN9") (pin "2") (pinfunction "2_2") (pintype "passive"))
    )
    (net (code "41") (name "Net-(MN10-Pad2)") (class "Default")
      (node (ref "MN10") (pin "2") (pinfunction "2_2") (pintype "passive"))
      (node (ref "MN8") (pin "1") (pinfunction "1_1") (pintype "passive"))
    )
    (net (code "42") (name "Net-(VT1-D)") (class "Default")
      (node (ref "R16") (pin "2") (pinfunction "2_2") (pintype "passive"))
      (node (ref "VT1") (pin "2") (pinfunction "D_2") (pintype "passive"))
    )
    (net (code "43") (name "Net-(VT1-G1)") (class "Default")
      (node (ref "R17") (pin "1") (pinfunction "1_1") (pintype "passive"))
      (node (ref "VT1") (pin "3") (pinfunction "G2_3") (pintype "passive"))
      (node (ref "VT1") (pin "4") (pinfunction "G1_4") (pintype "passive"))
    )
    (net (code "44") (name "Net-(VT1-S)") (class "Default")
      (node (ref "C16") (pin "2") (pinfunction "2_2") (pintype "passive"))
      (node (ref "R18") (pin "1") (pinfunction "1_1") (pintype "passive"))
      (node (ref "R19") (pin "1") (pinfunction "1_1") (pintype "passive"))
      (node (ref "R23") (pin "2") (pinfunction "2_2") (pintype "passive"))
      (node (ref "VT1") (pin "1") (pinfunction "S_1") (pintype "passive"))
      (node (ref "VT3") (pin "2") (pinfunction "D_2") (pintype "passive"))
    )
    (net (code "45") (name "Net-(VT2-D)") (class "Default")
      (node (ref "C27") (pin "2") (pinfunction "2_2") (pintype "passive"))
      (node (ref "R16") (pin "1") (pinfunction "1_1") (pintype "passive"))
      (node (ref "R18") (pin "2") (pinfunction "2_2") (pintype "passive"))
      (node (ref "R24") (pin "2") (pinfunction "2_2") (pintype "passive"))
      (node (ref "VT2") (pin "2") (pinfunction "D_2") (pintype "passive"))
    )
    (net (code "46") (name "Net-(VT2-G1)") (class "Default")
      (node (ref "R22") (pin "2") (pinfunction "2_2") (pintype "passive"))
      (node (ref "VT2") (pin "3") (pinfunction "G2_3") (pintype "passive"))
      (node (ref "VT2") (pin "4") (pinfunction "G1_4") (pintype "passive"))
    )
    (net (code "47") (name "Net-(VT3-G1)") (class "Default")
      (node (ref "R25") (pin "1") (pinfunction "1_1") (pintype "passive"))
      (node (ref "VT3") (pin "3") (pinfunction "G2_3") (pintype "passive"))
      (node (ref "VT3") (pin "4") (pinfunction "G1_4") (pintype "passive"))
    )
    (net (code "48") (name "VCC1P8_LMS") (class "Default")
      (node (ref "C10") (pin "2") (pinfunction "2_2") (pintype "passive"))
      (node (ref "C3") (pin "1") (pinfunction "1_1") (pintype "passive"))
      (node (ref "C4") (pin "2") (pinfunction "2_2") (pintype "passive"))
      (node (ref "C5") (pin "1") (pinfunction "1_1") (pintype "passive"))
      (node (ref "C6") (pin "2") (pinfunction "2_2") (pintype "passive"))
      (node (ref "C7") (pin "1") (pinfunction "1_1") (pintype "passive"))
      (node (ref "C8") (pin "1") (pinfunction "1_1") (pintype "passive"))
      (node (ref "C9") (pin "2") (pinfunction "2_2") (pintype "passive"))
      (node (ref "MN1") (pin "2") (pinfunction "2_2") (pintype "passive"))
      (node (ref "MN2") (pin "2") (pinfunction "2_2") (pintype "passive"))
      (node (ref "MN7") (pin "2") (pinfunction "2_2") (pintype "passive"))
      (node (ref "MN8") (pin "2") (pinfunction "2_2") (pintype "passive"))
      (node (ref "R19") (pin "2") (pinfunction "2_2") (pintype "passive"))
    )
    (net (code "49") (name "VCC3P3") (class "Default")
      (node (ref "R14") (pin "1") (pinfunction "1_1") (pintype "passive"))
      (node (ref "R20") (pin "1") (pinfunction "1_1") (pintype "passive"))
    )
    (net (code "50") (name "VCC5P0_USB") (class "Default")
      (node (ref "R15") (pin "1") (pinfunction "1_1") (pintype "passive"))
      (node (ref "R21") (pin "1") (pinfunction "1_1") (pintype "passive"))
    )
    (net (code "51") (name "unconnected-(IC1C-rfgn_l_RFE_1-PadAM12)") (class "Default")
      (node (ref "IC1") (pin "AM12") (pinfunction "rfgn_l_RFE_1_AM12") (pintype "passive+no_connect"))
    )
    (net (code "52") (name "unconnected-(IC1C-rfgp_l_RFE_1-PadAN11)") (class "Default")
      (node (ref "IC1") (pin "AN11") (pinfunction "rfgp_l_RFE_1_AN11") (pintype "passive+no_connect"))
    )
    (net (code "53") (name "unconnected-(IC1D-pa1on_2-PadC11)") (class "Default")
      (node (ref "IC1") (pin "C11") (pinfunction "pa1on_2_C11") (pintype "passive+no_connect"))
    )
    (net (code "54") (name "unconnected-(IC1D-pa1op_2-PadB12)") (class "Default")
      (node (ref "IC1") (pin "B12") (pinfunction "pa1op_2_B12") (pintype "passive+no_connect"))
    )
    (net (code "55") (name "unconnected-(IC1D-pa2on_2-PadB14)") (class "Default")
      (node (ref "IC1") (pin "B14") (pinfunction "pa2on_2_B14") (pintype "passive+no_connect"))
    )
    (net (code "56") (name "unconnected-(IC1D-pa2op_2-PadA13)") (class "Default")
      (node (ref "IC1") (pin "A13") (pinfunction "pa2op_2_A13") (pintype "passive+no_connect"))
    )
    (net (code "57") (name "unconnected-(IC1D-rfgn_h_RFE_2-PadAM8)") (class "Default")
      (node (ref "IC1") (pin "AM8") (pinfunction "rfgn_h_RFE_2_AM8") (pintype "passive+no_connect"))
    )
    (net (code "58") (name "unconnected-(IC1D-rfgn_l_RFE_2-PadAP6)") (class "Default")
      (node (ref "IC1") (pin "AP6") (pinfunction "rfgn_l_RFE_2_AP6") (pintype "passive+no_connect"))
    )
    (net (code "59") (name "unconnected-(IC1D-rfgn_w_RFE_2-PadAM4)") (class "Default")
      (node (ref "IC1") (pin "AM4") (pinfunction "rfgn_w_RFE_2_AM4") (pintype "passive+no_connect"))
    )
    (net (code "60") (name "unconnected-(IC1D-rfgp_h_RFE_2-PadAN7)") (class "Default")
      (node (ref "IC1") (pin "AN7") (pinfunction "rfgp_h_RFE_2_AN7") (pintype "passive+no_connect"))
    )
    (net (code "61") (name "unconnected-(IC1D-rfgp_l_RFE_2-PadAN5)") (class "Default")
      (node (ref "IC1") (pin "AN5") (pinfunction "rfgp_l_RFE_2_AN5") (pintype "passive+no_connect"))
    )
    (net (code "62") (name "unconnected-(IC1D-rfgp_w_RFE_2-PadAN3)") (class "Default")
      (node (ref "IC1") (pin "AN3") (pinfunction "rfgp_w_RFE_2_AN3") (pintype "passive+no_connect"))
    )
  )
)
